# DR55_soundgen.net
KiCad netlist of a schematic drawn in EAGLE
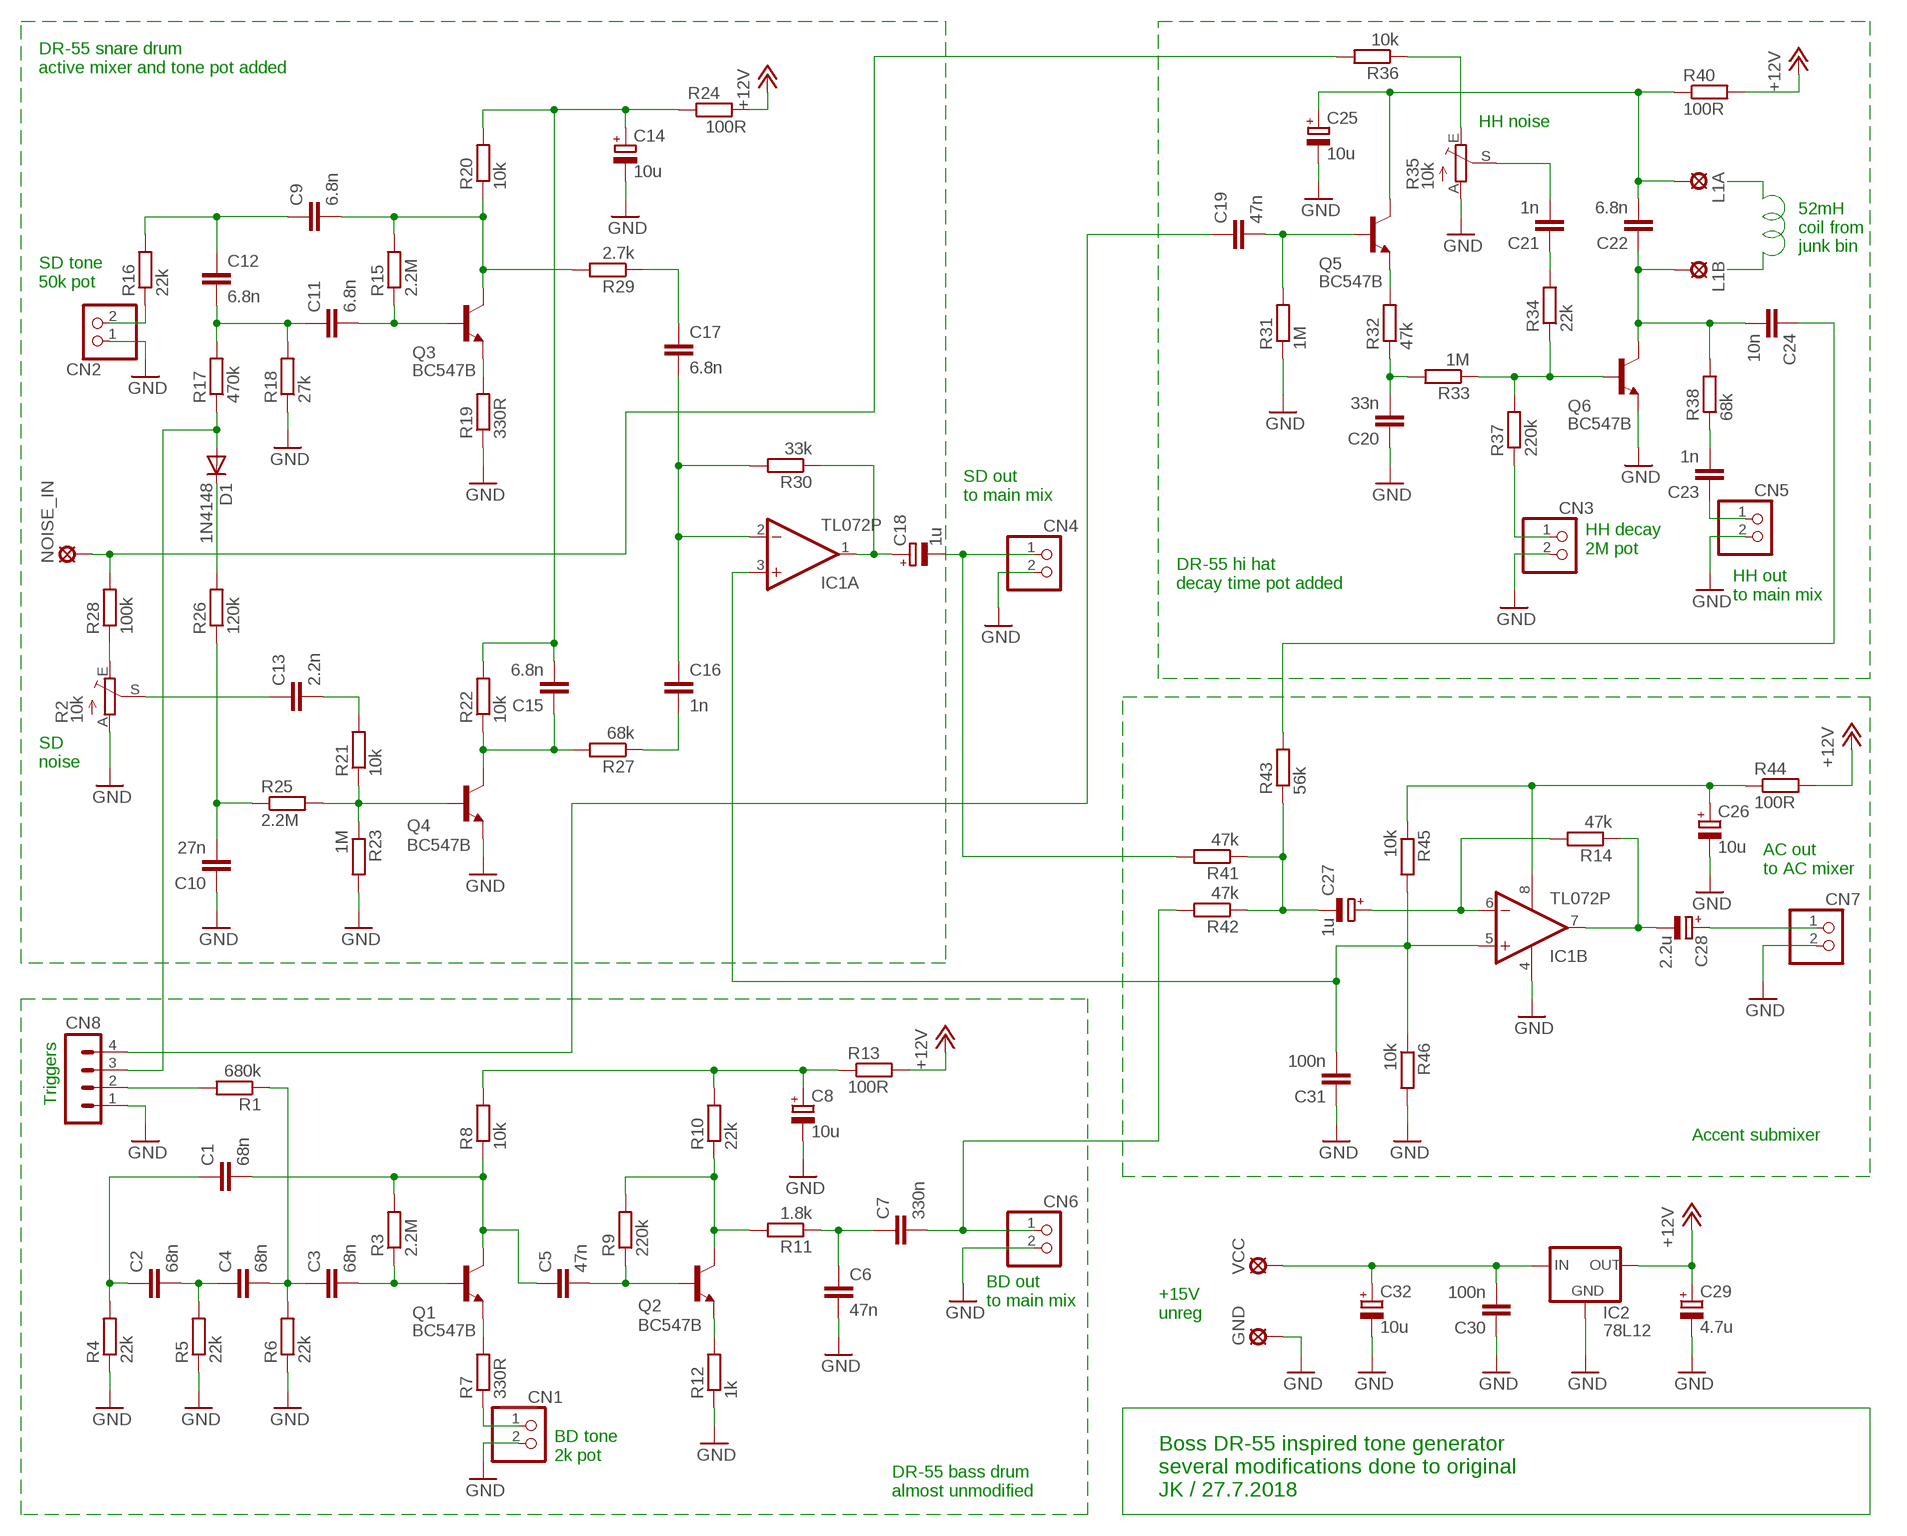
[diagram p0: schematic, sheet 1]

(export (version "E")
  (design (tool "Eeschema 10.0.6"))
  (components
    (comp (ref "C1")
      (value "68n")
      (footprint "eagle-import:C0805")
      (libsource (lib "eagle-import") (part "C-EUC0805"))
    )
    (comp (ref "C2")
      (value "68n")
      (footprint "eagle-import:C0805")
      (libsource (lib "eagle-import") (part "C-EUC0805"))
    )
    (comp (ref "C3")
      (value "68n")
      (footprint "eagle-import:C0805")
      (libsource (lib "eagle-import") (part "C-EUC0805"))
    )
    (comp (ref "C4")
      (value "68n")
      (footprint "eagle-import:C0805")
      (libsource (lib "eagle-import") (part "C-EUC0805"))
    )
    (comp (ref "C5")
      (value "47n")
      (footprint "eagle-import:C0805")
      (libsource (lib "eagle-import") (part "C-EUC0805"))
    )
    (comp (ref "C6")
      (value "47n")
      (footprint "eagle-import:C0805")
      (libsource (lib "eagle-import") (part "C-EUC0805"))
    )
    (comp (ref "C7")
      (value "330n")
      (footprint "eagle-import:C0805")
      (libsource (lib "eagle-import") (part "C-EUC0805"))
    )
    (comp (ref "C8")
      (value "10u")
      (footprint "eagle-import:E5-5")
      (libsource (lib "eagle-import") (part "CPOL-EUE5-5"))
    )
    (comp (ref "C9")
      (value "6.8n")
      (footprint "eagle-import:C0805")
      (libsource (lib "eagle-import") (part "C-EUC0805"))
    )
    (comp (ref "C10")
      (value "27n")
      (footprint "eagle-import:C0805")
      (libsource (lib "eagle-import") (part "C-EUC0805"))
    )
    (comp (ref "C11")
      (value "6.8n")
      (footprint "eagle-import:C0805")
      (libsource (lib "eagle-import") (part "C-EUC0805"))
    )
    (comp (ref "C12")
      (value "6.8n")
      (footprint "eagle-import:C0805")
      (libsource (lib "eagle-import") (part "C-EUC0805"))
    )
    (comp (ref "C13")
      (value "2.2n")
      (footprint "eagle-import:C0805")
      (libsource (lib "eagle-import") (part "C-EUC0805"))
    )
    (comp (ref "C14")
      (value "10u")
      (footprint "eagle-import:E5-5")
      (libsource (lib "eagle-import") (part "CPOL-EUE5-5"))
    )
    (comp (ref "C15")
      (value "6.8n")
      (footprint "eagle-import:C025-024X044")
      (libsource (lib "eagle-import") (part "C-EU025-024X044"))
    )
    (comp (ref "C16")
      (value "1n")
      (footprint "eagle-import:C0805")
      (libsource (lib "eagle-import") (part "C-EUC0805"))
    )
    (comp (ref "C17")
      (value "6.8n")
      (footprint "eagle-import:C0805")
      (libsource (lib "eagle-import") (part "C-EUC0805"))
    )
    (comp (ref "C18")
      (value "1u")
      (footprint "eagle-import:SMC_A")
      (libsource (lib "eagle-import") (part "CPOL-EUSMCA"))
    )
    (comp (ref "C19")
      (value "47n")
      (footprint "eagle-import:C0805")
      (libsource (lib "eagle-import") (part "C-EUC0805"))
    )
    (comp (ref "C20")
      (value "33n")
      (footprint "eagle-import:C0805")
      (libsource (lib "eagle-import") (part "C-EUC0805"))
    )
    (comp (ref "C21")
      (value "1n")
      (footprint "eagle-import:C0805")
      (libsource (lib "eagle-import") (part "C-EUC0805"))
    )
    (comp (ref "C22")
      (value "6.8n")
      (footprint "eagle-import:C0805")
      (libsource (lib "eagle-import") (part "C-EUC0805"))
    )
    (comp (ref "C23")
      (value "1n")
      (footprint "eagle-import:C0805")
      (libsource (lib "eagle-import") (part "C-EUC0805"))
    )
    (comp (ref "C24")
      (value "10n")
      (footprint "eagle-import:C0805")
      (libsource (lib "eagle-import") (part "C-EUC0805"))
    )
    (comp (ref "C25")
      (value "10u")
      (footprint "eagle-import:E5-5")
      (libsource (lib "eagle-import") (part "CPOL-EUE5-5"))
    )
    (comp (ref "C26")
      (value "10u")
      (footprint "eagle-import:E5-5")
      (libsource (lib "eagle-import") (part "CPOL-EUE5-5"))
    )
    (comp (ref "C27")
      (value "1u")
      (footprint "eagle-import:SMC_A")
      (libsource (lib "eagle-import") (part "CPOL-EUSMCA"))
    )
    (comp (ref "C28")
      (value "2.2u")
      (footprint "eagle-import:E5-5")
      (libsource (lib "eagle-import") (part "CPOL-EUE5-5"))
    )
    (comp (ref "C29")
      (value "4.7u")
      (footprint "eagle-import:SMC_A")
      (libsource (lib "eagle-import") (part "CPOL-EUSMCA"))
    )
    (comp (ref "C30")
      (value "100n")
      (footprint "eagle-import:C0805")
      (libsource (lib "eagle-import") (part "C-EUC0805"))
    )
    (comp (ref "C31")
      (value "100n")
      (footprint "eagle-import:C0805")
      (libsource (lib "eagle-import") (part "C-EUC0805"))
    )
    (comp (ref "C32")
      (value "10u")
      (footprint "eagle-import:E5-5")
      (libsource (lib "eagle-import") (part "CPOL-EUE5-5"))
    )
    (comp (ref "CN1")
      (value "PINHD-1X2")
      (footprint "eagle-import:1X02")
      (libsource (lib "eagle-import") (part "PINHD-1X2"))
    )
    (comp (ref "CN2")
      (value "PINHD-1X2")
      (footprint "eagle-import:1X02")
      (libsource (lib "eagle-import") (part "PINHD-1X2"))
    )
    (comp (ref "CN3")
      (value "PINHD-1X2")
      (footprint "eagle-import:1X02")
      (libsource (lib "eagle-import") (part "PINHD-1X2"))
    )
    (comp (ref "CN4")
      (value "PINHD-1X2")
      (footprint "eagle-import:1X02")
      (libsource (lib "eagle-import") (part "PINHD-1X2"))
    )
    (comp (ref "CN5")
      (value "PINHD-1X2")
      (footprint "eagle-import:1X02")
      (libsource (lib "eagle-import") (part "PINHD-1X2"))
    )
    (comp (ref "CN6")
      (value "PINHD-1X2")
      (footprint "eagle-import:1X02")
      (libsource (lib "eagle-import") (part "PINHD-1X2"))
    )
    (comp (ref "CN7")
      (value "PINHD-1X2")
      (footprint "eagle-import:1X02")
      (libsource (lib "eagle-import") (part "PINHD-1X2"))
    )
    (comp (ref "CN8")
      (value "MA04-1")
      (footprint "eagle-import:MA04-1")
      (libsource (lib "eagle-import") (part "MA04-1"))
    )
    (comp (ref "D1")
      (value "1N4148")
      (footprint "eagle-import:SOD80C")
      (libsource (lib "eagle-import") (part "DIODE-SOD80C"))
    )
    (comp (ref "GND")
      (value "LSP10")
      (footprint "eagle-import:LSP10")
      (libsource (lib "eagle-import") (part "LSP10"))
    )
    (comp (ref "IC1")
      (value "TL072P")
      (footprint "eagle-import:DIL08")
      (libsource (lib "eagle-import") (part "TL072P"))
    )
    (comp (ref "IC2")
      (value "78L12")
      (footprint "eagle-import:78LXX")
      (libsource (lib "eagle-import") (part "78LXX"))
    )
    (comp (ref "L1A")
      (value "MCS10B")
      (footprint "eagle-import:MCS10B")
      (libsource (lib "eagle-import") (part "MCS10B"))
    )
    (comp (ref "L1B")
      (value "MCS10B")
      (footprint "eagle-import:MCS10B")
      (libsource (lib "eagle-import") (part "MCS10B"))
    )
    (comp (ref "NOISE_IN")
      (value "LSP10")
      (footprint "eagle-import:LSP10")
      (libsource (lib "eagle-import") (part "LSP10"))
    )
    (comp (ref "Q1")
      (value "BC547B")
      (footprint "eagle-import:TO92")
      (libsource (lib "eagle-import") (part "BC547B"))
    )
    (comp (ref "Q2")
      (value "BC547B")
      (footprint "eagle-import:TO92")
      (libsource (lib "eagle-import") (part "BC547B"))
    )
    (comp (ref "Q3")
      (value "BC547B")
      (footprint "eagle-import:TO92")
      (libsource (lib "eagle-import") (part "BC547B"))
    )
    (comp (ref "Q4")
      (value "BC547B")
      (footprint "eagle-import:TO92")
      (libsource (lib "eagle-import") (part "BC547B"))
    )
    (comp (ref "Q5")
      (value "BC547B")
      (footprint "eagle-import:TO92")
      (libsource (lib "eagle-import") (part "BC547B"))
    )
    (comp (ref "Q6")
      (value "BC547B")
      (footprint "eagle-import:TO92")
      (libsource (lib "eagle-import") (part "BC547B"))
    )
    (comp (ref "R1")
      (value "680k")
      (footprint "eagle-import:R0805")
      (libsource (lib "eagle-import") (part "R-EU_R0805"))
    )
    (comp (ref "R2")
      (value "10k")
      (footprint "eagle-import:S63X")
      (libsource (lib "eagle-import") (part "TRIM_EU-S63X"))
    )
    (comp (ref "R3")
      (value "2.2M")
      (footprint "eagle-import:R0805")
      (libsource (lib "eagle-import") (part "R-EU_R0805"))
    )
    (comp (ref "R4")
      (value "22k")
      (footprint "eagle-import:R0805")
      (libsource (lib "eagle-import") (part "R-EU_R0805"))
    )
    (comp (ref "R5")
      (value "22k")
      (footprint "eagle-import:R0805")
      (libsource (lib "eagle-import") (part "R-EU_R0805"))
    )
    (comp (ref "R6")
      (value "22k")
      (footprint "eagle-import:R0805")
      (libsource (lib "eagle-import") (part "R-EU_R0805"))
    )
    (comp (ref "R7")
      (value "330R")
      (footprint "eagle-import:R0805")
      (libsource (lib "eagle-import") (part "R-EU_R0805"))
    )
    (comp (ref "R8")
      (value "10k")
      (footprint "eagle-import:R0805")
      (libsource (lib "eagle-import") (part "R-EU_R0805"))
    )
    (comp (ref "R9")
      (value "220k")
      (footprint "eagle-import:R0805")
      (libsource (lib "eagle-import") (part "R-EU_R0805"))
    )
    (comp (ref "R10")
      (value "22k")
      (footprint "eagle-import:R0805")
      (libsource (lib "eagle-import") (part "R-EU_R0805"))
    )
    (comp (ref "R11")
      (value "1.8k")
      (footprint "eagle-import:R0805")
      (libsource (lib "eagle-import") (part "R-EU_R0805"))
    )
    (comp (ref "R12")
      (value "1k")
      (footprint "eagle-import:R0805")
      (libsource (lib "eagle-import") (part "R-EU_R0805"))
    )
    (comp (ref "R13")
      (value "100R")
      (footprint "eagle-import:R0805")
      (libsource (lib "eagle-import") (part "R-EU_R0805"))
    )
    (comp (ref "R14")
      (value "47k")
      (footprint "eagle-import:R0805")
      (libsource (lib "eagle-import") (part "R-EU_R0805"))
    )
    (comp (ref "R15")
      (value "2.2M")
      (footprint "eagle-import:R0805")
      (libsource (lib "eagle-import") (part "R-EU_R0805"))
    )
    (comp (ref "R16")
      (value "22k")
      (footprint "eagle-import:R0805")
      (libsource (lib "eagle-import") (part "R-EU_R0805"))
    )
    (comp (ref "R17")
      (value "470k")
      (footprint "eagle-import:R0805")
      (libsource (lib "eagle-import") (part "R-EU_R0805"))
    )
    (comp (ref "R18")
      (value "27k")
      (footprint "eagle-import:R0805")
      (libsource (lib "eagle-import") (part "R-EU_R0805"))
    )
    (comp (ref "R19")
      (value "330R")
      (footprint "eagle-import:R0805")
      (libsource (lib "eagle-import") (part "R-EU_R0805"))
    )
    (comp (ref "R20")
      (value "10k")
      (footprint "eagle-import:R0805")
      (libsource (lib "eagle-import") (part "R-EU_R0805"))
    )
    (comp (ref "R21")
      (value "10k")
      (footprint "eagle-import:R0805")
      (libsource (lib "eagle-import") (part "R-EU_R0805"))
    )
    (comp (ref "R22")
      (value "10k")
      (footprint "eagle-import:R0805")
      (libsource (lib "eagle-import") (part "R-EU_R0805"))
    )
    (comp (ref "R23")
      (value "1M")
      (footprint "eagle-import:R0805")
      (libsource (lib "eagle-import") (part "R-EU_R0805"))
    )
    (comp (ref "R24")
      (value "100R")
      (footprint "eagle-import:R0805")
      (libsource (lib "eagle-import") (part "R-EU_R0805"))
    )
    (comp (ref "R25")
      (value "2.2M")
      (footprint "eagle-import:R0805")
      (libsource (lib "eagle-import") (part "R-EU_R0805"))
    )
    (comp (ref "R26")
      (value "120k")
      (footprint "eagle-import:R0805")
      (libsource (lib "eagle-import") (part "R-EU_R0805"))
    )
    (comp (ref "R27")
      (value "68k")
      (footprint "eagle-import:R0805")
      (libsource (lib "eagle-import") (part "R-EU_R0805"))
    )
    (comp (ref "R28")
      (value "100k")
      (footprint "eagle-import:R0805")
      (libsource (lib "eagle-import") (part "R-EU_R0805"))
    )
    (comp (ref "R29")
      (value "2.7k")
      (footprint "eagle-import:R0805")
      (libsource (lib "eagle-import") (part "R-EU_R0805"))
    )
    (comp (ref "R30")
      (value "33k")
      (footprint "eagle-import:R0805")
      (libsource (lib "eagle-import") (part "R-EU_R0805"))
    )
    (comp (ref "R31")
      (value "1M")
      (footprint "eagle-import:R0805")
      (libsource (lib "eagle-import") (part "R-EU_R0805"))
    )
    (comp (ref "R32")
      (value "47k")
      (footprint "eagle-import:0207_10")
      (libsource (lib "eagle-import") (part "R-EU_0207/10"))
    )
    (comp (ref "R33")
      (value "1M")
      (footprint "eagle-import:R0805")
      (libsource (lib "eagle-import") (part "R-EU_R0805"))
    )
    (comp (ref "R34")
      (value "22k")
      (footprint "eagle-import:R0805")
      (libsource (lib "eagle-import") (part "R-EU_R0805"))
    )
    (comp (ref "R35")
      (value "10k")
      (footprint "eagle-import:S63X")
      (libsource (lib "eagle-import") (part "TRIM_EU-S63X"))
    )
    (comp (ref "R36")
      (value "10k")
      (footprint "eagle-import:R0805")
      (libsource (lib "eagle-import") (part "R-EU_R0805"))
    )
    (comp (ref "R37")
      (value "220k")
      (footprint "eagle-import:R0805")
      (libsource (lib "eagle-import") (part "R-EU_R0805"))
    )
    (comp (ref "R38")
      (value "68k")
      (footprint "eagle-import:R0805")
      (libsource (lib "eagle-import") (part "R-EU_R0805"))
    )
    (comp (ref "R40")
      (value "100R")
      (footprint "eagle-import:R0805")
      (libsource (lib "eagle-import") (part "R-EU_R0805"))
    )
    (comp (ref "R41")
      (value "47k")
      (footprint "eagle-import:R0805")
      (libsource (lib "eagle-import") (part "R-EU_R0805"))
    )
    (comp (ref "R42")
      (value "47k")
      (footprint "eagle-import:R0805")
      (libsource (lib "eagle-import") (part "R-EU_R0805"))
    )
    (comp (ref "R43")
      (value "56k")
      (footprint "eagle-import:R0805")
      (libsource (lib "eagle-import") (part "R-EU_R0805"))
    )
    (comp (ref "R44")
      (value "100R")
      (footprint "eagle-import:R0805")
      (libsource (lib "eagle-import") (part "R-EU_R0805"))
    )
    (comp (ref "R45")
      (value "10k")
      (footprint "eagle-import:R0805")
      (libsource (lib "eagle-import") (part "R-EU_R0805"))
    )
    (comp (ref "R46")
      (value "10k")
      (footprint "eagle-import:R0805")
      (libsource (lib "eagle-import") (part "R-EU_R0805"))
    )
    (comp (ref "VCC")
      (value "LSP10")
      (footprint "eagle-import:LSP10")
      (libsource (lib "eagle-import") (part "LSP10"))
    )
  )
  (nets
    (net (code "1") (name "+12V") (class "Default")
      (node (ref "C29") (pin "+") (pinfunction "+_+") (pintype "passive"))
      (node (ref "IC2") (pin "OUT") (pinfunction "OUT_OUT") (pintype "passive"))
      (node (ref "R13") (pin "2") (pinfunction "2_2") (pintype "passive"))
      (node (ref "R24") (pin "2") (pinfunction "2_2") (pintype "passive"))
      (node (ref "R40") (pin "2") (pinfunction "2_2") (pintype "passive"))
      (node (ref "R44") (pin "2") (pinfunction "2_2") (pintype "passive"))
    )
    (net (code "2") (name "GND") (class "Default")
      (node (ref "C10") (pin "1") (pinfunction "1_1") (pintype "passive"))
      (node (ref "C14") (pin "-") (pinfunction "-_-") (pintype "passive"))
      (node (ref "C20") (pin "1") (pinfunction "1_1") (pintype "passive"))
      (node (ref "C25") (pin "-") (pinfunction "-_-") (pintype "passive"))
      (node (ref "C26") (pin "-") (pinfunction "-_-") (pintype "passive"))
      (node (ref "C29") (pin "-") (pinfunction "-_-") (pintype "passive"))
      (node (ref "C30") (pin "1") (pinfunction "1_1") (pintype "passive"))
      (node (ref "C31") (pin "1") (pinfunction "1_1") (pintype "passive"))
      (node (ref "C32") (pin "-") (pinfunction "-_-") (pintype "passive"))
      (node (ref "C6") (pin "2") (pinfunction "2_2") (pintype "passive"))
      (node (ref "C8") (pin "-") (pinfunction "-_-") (pintype "passive"))
      (node (ref "CN1") (pin "2") (pinfunction "2_2") (pintype "passive"))
      (node (ref "CN2") (pin "1") (pinfunction "1_1") (pintype "passive"))
      (node (ref "CN3") (pin "2") (pinfunction "2_2") (pintype "passive"))
      (node (ref "CN4") (pin "2") (pinfunction "2_2") (pintype "passive"))
      (node (ref "CN5") (pin "2") (pinfunction "2_2") (pintype "passive"))
      (node (ref "CN6") (pin "2") (pinfunction "2_2") (pintype "passive"))
      (node (ref "CN7") (pin "2") (pinfunction "2_2") (pintype "passive"))
      (node (ref "CN8") (pin "1") (pinfunction "1_1") (pintype "passive"))
      (node (ref "GND") (pin "MP") (pinfunction "MP_MP") (pintype "passive"))
      (node (ref "IC1") (pin "4") (pinfunction "V-_4") (pintype "power_in"))
      (node (ref "IC2") (pin "GND") (pinfunction "GND_GND") (pintype "input"))
      (node (ref "Q4") (pin "1") (pinfunction "E_1") (pintype "passive"))
      (node (ref "Q6") (pin "1") (pinfunction "E_1") (pintype "passive"))
      (node (ref "R12") (pin "1") (pinfunction "1_1") (pintype "passive"))
      (node (ref "R18") (pin "1") (pinfunction "1_1") (pintype "passive"))
      (node (ref "R19") (pin "1") (pinfunction "1_1") (pintype "passive"))
      (node (ref "R2") (pin "A") (pinfunction "A_A") (pintype "passive"))
      (node (ref "R23") (pin "2") (pinfunction "2_2") (pintype "passive"))
      (node (ref "R31") (pin "1") (pinfunction "1_1") (pintype "passive"))
      (node (ref "R35") (pin "A") (pinfunction "A_A") (pintype "passive"))
      (node (ref "R4") (pin "1") (pinfunction "1_1") (pintype "passive"))
      (node (ref "R46") (pin "2") (pinfunction "2_2") (pintype "passive"))
      (node (ref "R5") (pin "1") (pinfunction "1_1") (pintype "passive"))
      (node (ref "R6") (pin "1") (pinfunction "1_1") (pintype "passive"))
    )
    (net (code "3") (name "Net-(C1-Pad1)") (class "Default")
      (node (ref "C1") (pin "1") (pinfunction "1_1") (pintype "passive"))
      (node (ref "C2") (pin "1") (pinfunction "1_1") (pintype "passive"))
      (node (ref "R4") (pin "2") (pinfunction "2_2") (pintype "passive"))
    )
    (net (code "4") (name "Net-(C2-Pad2)") (class "Default")
      (node (ref "C2") (pin "2") (pinfunction "2_2") (pintype "passive"))
      (node (ref "C4") (pin "1") (pinfunction "1_1") (pintype "passive"))
      (node (ref "R5") (pin "2") (pinfunction "2_2") (pintype "passive"))
    )
    (net (code "5") (name "Net-(C3-Pad1)") (class "Default")
      (node (ref "C3") (pin "1") (pinfunction "1_1") (pintype "passive"))
      (node (ref "C4") (pin "2") (pinfunction "2_2") (pintype "passive"))
      (node (ref "R1") (pin "1") (pinfunction "1_1") (pintype "passive"))
      (node (ref "R6") (pin "2") (pinfunction "2_2") (pintype "passive"))
    )
    (net (code "6") (name "Net-(C6-Pad1)") (class "Default")
      (node (ref "C6") (pin "1") (pinfunction "1_1") (pintype "passive"))
      (node (ref "C7") (pin "1") (pinfunction "1_1") (pintype "passive"))
      (node (ref "R11") (pin "1") (pinfunction "1_1") (pintype "passive"))
    )
    (net (code "7") (name "Net-(C7-Pad2)") (class "Default")
      (node (ref "C7") (pin "2") (pinfunction "2_2") (pintype "passive"))
      (node (ref "CN6") (pin "1") (pinfunction "1_1") (pintype "passive"))
      (node (ref "R42") (pin "2") (pinfunction "2_2") (pintype "passive"))
    )
    (net (code "8") (name "Net-(C8-Pad+)") (class "Default")
      (node (ref "C8") (pin "+") (pinfunction "+_+") (pintype "passive"))
      (node (ref "R10") (pin "2") (pinfunction "2_2") (pintype "passive"))
      (node (ref "R13") (pin "1") (pinfunction "1_1") (pintype "passive"))
      (node (ref "R8") (pin "2") (pinfunction "2_2") (pintype "passive"))
    )
    (net (code "9") (name "Net-(C10-Pad2)") (class "Default")
      (node (ref "C10") (pin "2") (pinfunction "2_2") (pintype "passive"))
      (node (ref "R25") (pin "1") (pinfunction "1_1") (pintype "passive"))
      (node (ref "R26") (pin "1") (pinfunction "1_1") (pintype "passive"))
    )
    (net (code "10") (name "Net-(C11-Pad1)") (class "Default")
      (node (ref "C11") (pin "1") (pinfunction "1_1") (pintype "passive"))
      (node (ref "C12") (pin "2") (pinfunction "2_2") (pintype "passive"))
      (node (ref "R17") (pin "2") (pinfunction "2_2") (pintype "passive"))
      (node (ref "R18") (pin "2") (pinfunction "2_2") (pintype "passive"))
    )
    (net (code "11") (name "Net-(C12-Pad1)") (class "Default")
      (node (ref "C12") (pin "1") (pinfunction "1_1") (pintype "passive"))
      (node (ref "C9") (pin "1") (pinfunction "1_1") (pintype "passive"))
      (node (ref "R16") (pin "2") (pinfunction "2_2") (pintype "passive"))
    )
    (net (code "12") (name "Net-(C13-Pad1)") (class "Default")
      (node (ref "C13") (pin "1") (pinfunction "1_1") (pintype "passive"))
      (node (ref "R2") (pin "S") (pinfunction "S_S") (pintype "passive"))
    )
    (net (code "13") (name "Net-(C13-Pad2)") (class "Default")
      (node (ref "C13") (pin "2") (pinfunction "2_2") (pintype "passive"))
      (node (ref "R21") (pin "2") (pinfunction "2_2") (pintype "passive"))
    )
    (net (code "14") (name "Net-(C14-Pad+)") (class "Default")
      (node (ref "C14") (pin "+") (pinfunction "+_+") (pintype "passive"))
      (node (ref "C15") (pin "2") (pinfunction "2_2") (pintype "passive"))
      (node (ref "R20") (pin "2") (pinfunction "2_2") (pintype "passive"))
      (node (ref "R22") (pin "2") (pinfunction "2_2") (pintype "passive"))
      (node (ref "R24") (pin "1") (pinfunction "1_1") (pintype "passive"))
    )
    (net (code "15") (name "Net-(C16-Pad2)") (class "Default")
      (node (ref "C16") (pin "2") (pinfunction "2_2") (pintype "passive"))
      (node (ref "R27") (pin "1") (pinfunction "1_1") (pintype "passive"))
    )
    (net (code "16") (name "Net-(C17-Pad1)") (class "Default")
      (node (ref "C17") (pin "1") (pinfunction "1_1") (pintype "passive"))
      (node (ref "R29") (pin "1") (pinfunction "1_1") (pintype "passive"))
    )
    (net (code "17") (name "Net-(C18-Pad-)") (class "Default")
      (node (ref "C18") (pin "-") (pinfunction "-_-") (pintype "passive"))
      (node (ref "CN4") (pin "1") (pinfunction "1_1") (pintype "passive"))
      (node (ref "R41") (pin "2") (pinfunction "2_2") (pintype "passive"))
    )
    (net (code "18") (name "Net-(C19-Pad1)") (class "Default")
      (node (ref "C19") (pin "1") (pinfunction "1_1") (pintype "passive"))
      (node (ref "CN8") (pin "4") (pinfunction "4_4") (pintype "passive"))
    )
    (net (code "19") (name "Net-(C20-Pad2)") (class "Default")
      (node (ref "C20") (pin "2") (pinfunction "2_2") (pintype "passive"))
      (node (ref "R32") (pin "1") (pinfunction "1_1") (pintype "passive"))
      (node (ref "R33") (pin "2") (pinfunction "2_2") (pintype "passive"))
    )
    (net (code "20") (name "Net-(C21-Pad1)") (class "Default")
      (node (ref "C21") (pin "1") (pinfunction "1_1") (pintype "passive"))
      (node (ref "R34") (pin "2") (pinfunction "2_2") (pintype "passive"))
    )
    (net (code "21") (name "Net-(C21-Pad2)") (class "Default")
      (node (ref "C21") (pin "2") (pinfunction "2_2") (pintype "passive"))
      (node (ref "R35") (pin "S") (pinfunction "S_S") (pintype "passive"))
    )
    (net (code "22") (name "Net-(C23-Pad1)") (class "Default")
      (node (ref "C23") (pin "1") (pinfunction "1_1") (pintype "passive"))
      (node (ref "CN5") (pin "1") (pinfunction "1_1") (pintype "passive"))
    )
    (net (code "23") (name "Net-(C23-Pad2)") (class "Default")
      (node (ref "C23") (pin "2") (pinfunction "2_2") (pintype "passive"))
      (node (ref "R38") (pin "1") (pinfunction "1_1") (pintype "passive"))
    )
    (net (code "24") (name "Net-(C24-Pad1)") (class "Default")
      (node (ref "C24") (pin "1") (pinfunction "1_1") (pintype "passive"))
      (node (ref "R43") (pin "2") (pinfunction "2_2") (pintype "passive"))
    )
    (net (code "25") (name "Net-(C27-Pad-)") (class "Default")
      (node (ref "C27") (pin "-") (pinfunction "-_-") (pintype "passive"))
      (node (ref "R41") (pin "1") (pinfunction "1_1") (pintype "passive"))
      (node (ref "R42") (pin "1") (pinfunction "1_1") (pintype "passive"))
      (node (ref "R43") (pin "1") (pinfunction "1_1") (pintype "passive"))
    )
    (net (code "26") (name "Net-(C28-Pad+)") (class "Default")
      (node (ref "C28") (pin "+") (pinfunction "+_+") (pintype "passive"))
      (node (ref "CN7") (pin "1") (pinfunction "1_1") (pintype "passive"))
    )
    (net (code "27") (name "Net-(C30-Pad2)") (class "Default")
      (node (ref "C30") (pin "2") (pinfunction "2_2") (pintype "passive"))
      (node (ref "C32") (pin "+") (pinfunction "+_+") (pintype "passive"))
      (node (ref "IC2") (pin "IN") (pinfunction "IN_IN") (pintype "input"))
      (node (ref "VCC") (pin "MP") (pinfunction "MP_MP") (pintype "passive"))
    )
    (net (code "28") (name "Net-(CN1-Pad1)") (class "Default")
      (node (ref "CN1") (pin "1") (pinfunction "1_1") (pintype "passive"))
      (node (ref "R7") (pin "1") (pinfunction "1_1") (pintype "passive"))
    )
    (net (code "29") (name "Net-(CN2-Pad2)") (class "Default")
      (node (ref "CN2") (pin "2") (pinfunction "2_2") (pintype "passive"))
      (node (ref "R16") (pin "1") (pinfunction "1_1") (pintype "passive"))
    )
    (net (code "30") (name "Net-(CN3-Pad1)") (class "Default")
      (node (ref "CN3") (pin "1") (pinfunction "1_1") (pintype "passive"))
      (node (ref "R37") (pin "1") (pinfunction "1_1") (pintype "passive"))
    )
    (net (code "31") (name "Net-(CN8-Pad2)") (class "Default")
      (node (ref "CN8") (pin "2") (pinfunction "2_2") (pintype "passive"))
      (node (ref "R1") (pin "2") (pinfunction "2_2") (pintype "passive"))
    )
    (net (code "32") (name "Net-(CN8-Pad3)") (class "Default")
      (node (ref "CN8") (pin "3") (pinfunction "3_3") (pintype "passive"))
      (node (ref "D1") (pin "A") (pinfunction "A_A") (pintype "passive"))
      (node (ref "R17") (pin "1") (pinfunction "1_1") (pintype "passive"))
    )
    (net (code "33") (name "Net-(D1-PadC)") (class "Default")
      (node (ref "D1") (pin "C") (pinfunction "C_C") (pintype "passive"))
      (node (ref "R26") (pin "2") (pinfunction "2_2") (pintype "passive"))
    )
    (net (code "34") (name "Net-(IC1A-+IN)") (class "Default")
      (node (ref "C31") (pin "2") (pinfunction "2_2") (pintype "passive"))
      (node (ref "IC1") (pin "3") (pinfunction "+IN_3") (pintype "input"))
      (node (ref "IC1") (pin "5") (pinfunction "+IN_5") (pintype "input"))
      (node (ref "R45") (pin "2") (pinfunction "2_2") (pintype "passive"))
      (node (ref "R46") (pin "1") (pinfunction "1_1") (pintype "passive"))
    )
    (net (code "35") (name "Net-(IC1A--IN)") (class "Default")
      (node (ref "C16") (pin "1") (pinfunction "1_1") (pintype "passive"))
      (node (ref "C17") (pin "2") (pinfunction "2_2") (pintype "passive"))
      (node (ref "IC1") (pin "2") (pinfunction "-IN_2") (pintype "input"))
      (node (ref "R30") (pin "2") (pinfunction "2_2") (pintype "passive"))
    )
    (net (code "36") (name "Net-(IC1A-OUT)") (class "Default")
      (node (ref "C18") (pin "+") (pinfunction "+_+") (pintype "passive"))
      (node (ref "IC1") (pin "1") (pinfunction "OUT_1") (pintype "output"))
      (node (ref "R30") (pin "1") (pinfunction "1_1") (pintype "passive"))
    )
    (net (code "37") (name "Net-(IC1B--IN)") (class "Default")
      (node (ref "C27") (pin "+") (pinfunction "+_+") (pintype "passive"))
      (node (ref "IC1") (pin "6") (pinfunction "-IN_6") (pintype "input"))
      (node (ref "R14") (pin "2") (pinfunction "2_2") (pintype "passive"))
    )
    (net (code "38") (name "Net-(IC1B-OUT)") (class "Default")
      (node (ref "C28") (pin "-") (pinfunction "-_-") (pintype "passive"))
      (node (ref "IC1") (pin "7") (pinfunction "OUT_7") (pintype "output"))
      (node (ref "R14") (pin "1") (pinfunction "1_1") (pintype "passive"))
    )
    (net (code "39") (name "Net-(IC1C-V+)") (class "Default")
      (node (ref "C26") (pin "+") (pinfunction "+_+") (pintype "passive"))
      (node (ref "IC1") (pin "8") (pinfunction "V+_8") (pintype "power_in"))
      (node (ref "R44") (pin "1") (pinfunction "1_1") (pintype "passive"))
      (node (ref "R45") (pin "1") (pinfunction "1_1") (pintype "passive"))
    )
    (net (code "40") (name "Net-(NOISE_IN-PadMP)") (class "Default")
      (node (ref "NOISE_IN") (pin "MP") (pinfunction "MP_MP") (pintype "passive"))
      (node (ref "R28") (pin "2") (pinfunction "2_2") (pintype "passive"))
      (node (ref "R36") (pin "2") (pinfunction "2_2") (pintype "passive"))
    )
    (net (code "41") (name "Net-(Q1-B)") (class "Default")
      (node (ref "C3") (pin "2") (pinfunction "2_2") (pintype "passive"))
      (node (ref "Q1") (pin "2") (pinfunction "B_2") (pintype "passive"))
      (node (ref "R3") (pin "1") (pinfunction "1_1") (pintype "passive"))
    )
    (net (code "42") (name "Net-(Q1-C)") (class "Default")
      (node (ref "C1") (pin "2") (pinfunction "2_2") (pintype "passive"))
      (node (ref "C5") (pin "1") (pinfunction "1_1") (pintype "passive"))
      (node (ref "Q1") (pin "3") (pinfunction "C_3") (pintype "passive"))
      (node (ref "R3") (pin "2") (pinfunction "2_2") (pintype "passive"))
      (node (ref "R8") (pin "1") (pinfunction "1_1") (pintype "passive"))
    )
    (net (code "43") (name "Net-(Q1-E)") (class "Default")
      (node (ref "Q1") (pin "1") (pinfunction "E_1") (pintype "passive"))
      (node (ref "R7") (pin "2") (pinfunction "2_2") (pintype "passive"))
    )
    (net (code "44") (name "Net-(Q2-B)") (class "Default")
      (node (ref "C5") (pin "2") (pinfunction "2_2") (pintype "passive"))
      (node (ref "Q2") (pin "2") (pinfunction "B_2") (pintype "passive"))
      (node (ref "R9") (pin "1") (pinfunction "1_1") (pintype "passive"))
    )
    (net (code "45") (name "Net-(Q2-C)") (class "Default")
      (node (ref "Q2") (pin "3") (pinfunction "C_3") (pintype "passive"))
      (node (ref "R10") (pin "1") (pinfunction "1_1") (pintype "passive"))
      (node (ref "R11") (pin "2") (pinfunction "2_2") (pintype "passive"))
      (node (ref "R9") (pin "2") (pinfunction "2_2") (pintype "passive"))
    )
    (net (code "46") (name "Net-(Q2-E)") (class "Default")
      (node (ref "Q2") (pin "1") (pinfunction "E_1") (pintype "passive"))
      (node (ref "R12") (pin "2") (pinfunction "2_2") (pintype "passive"))
    )
    (net (code "47") (name "Net-(Q3-B)") (class "Default")
      (node (ref "C11") (pin "2") (pinfunction "2_2") (pintype "passive"))
      (node (ref "Q3") (pin "2") (pinfunction "B_2") (pintype "passive"))
      (node (ref "R15") (pin "1") (pinfunction "1_1") (pintype "passive"))
    )
    (net (code "48") (name "Net-(Q3-C)") (class "Default")
      (node (ref "C9") (pin "2") (pinfunction "2_2") (pintype "passive"))
      (node (ref "Q3") (pin "3") (pinfunction "C_3") (pintype "passive"))
      (node (ref "R15") (pin "2") (pinfunction "2_2") (pintype "passive"))
      (node (ref "R20") (pin "1") (pinfunction "1_1") (pintype "passive"))
      (node (ref "R29") (pin "2") (pinfunction "2_2") (pintype "passive"))
    )
    (net (code "49") (name "Net-(Q3-E)") (class "Default")
      (node (ref "Q3") (pin "1") (pinfunction "E_1") (pintype "passive"))
      (node (ref "R19") (pin "2") (pinfunction "2_2") (pintype "passive"))
    )
    (net (code "50") (name "Net-(Q4-B)") (class "Default")
      (node (ref "Q4") (pin "2") (pinfunction "B_2") (pintype "passive"))
      (node (ref "R21") (pin "1") (pinfunction "1_1") (pintype "passive"))
      (node (ref "R23") (pin "1") (pinfunction "1_1") (pintype "passive"))
      (node (ref "R25") (pin "2") (pinfunction "2_2") (pintype "passive"))
    )
    (net (code "51") (name "Net-(Q4-C)") (class "Default")
      (node (ref "C15") (pin "1") (pinfunction "1_1") (pintype "passive"))
      (node (ref "Q4") (pin "3") (pinfunction "C_3") (pintype "passive"))
      (node (ref "R22") (pin "1") (pinfunction "1_1") (pintype "passive"))
      (node (ref "R27") (pin "2") (pinfunction "2_2") (pintype "passive"))
    )
    (net (code "52") (name "Net-(Q5-B)") (class "Default")
      (node (ref "C19") (pin "2") (pinfunction "2_2") (pintype "passive"))
      (node (ref "Q5") (pin "2") (pinfunction "B_2") (pintype "passive"))
      (node (ref "R31") (pin "2") (pinfunction "2_2") (pintype "passive"))
    )
    (net (code "53") (name "Net-(Q5-C)") (class "Default")
      (node (ref "C22") (pin "2") (pinfunction "2_2") (pintype "passive"))
      (node (ref "C25") (pin "+") (pinfunction "+_+") (pintype "passive"))
      (node (ref "L1A") (pin "MP") (pinfunction "MP_MP") (pintype "passive"))
      (node (ref "Q5") (pin "3") (pinfunction "C_3") (pintype "passive"))
      (node (ref "R40") (pin "1") (pinfunction "1_1") (pintype "passive"))
    )
    (net (code "54") (name "Net-(Q5-E)") (class "Default")
      (node (ref "Q5") (pin "1") (pinfunction "E_1") (pintype "passive"))
      (node (ref "R32") (pin "2") (pinfunction "2_2") (pintype "passive"))
    )
    (net (code "55") (name "Net-(Q6-B)") (class "Default")
      (node (ref "Q6") (pin "2") (pinfunction "B_2") (pintype "passive"))
      (node (ref "R33") (pin "1") (pinfunction "1_1") (pintype "passive"))
      (node (ref "R34") (pin "1") (pinfunction "1_1") (pintype "passive"))
      (node (ref "R37") (pin "2") (pinfunction "2_2") (pintype "passive"))
    )
    (net (code "56") (name "Net-(Q6-C)") (class "Default")
      (node (ref "C22") (pin "1") (pinfunction "1_1") (pintype "passive"))
      (node (ref "C24") (pin "2") (pinfunction "2_2") (pintype "passive"))
      (node (ref "L1B") (pin "MP") (pinfunction "MP_MP") (pintype "passive"))
      (node (ref "Q6") (pin "3") (pinfunction "C_3") (pintype "passive"))
      (node (ref "R38") (pin "2") (pinfunction "2_2") (pintype "passive"))
    )
    (net (code "57") (name "Net-(R2-PadE)") (class "Default")
      (node (ref "R2") (pin "E") (pinfunction "E_E") (pintype "passive"))
      (node (ref "R28") (pin "1") (pinfunction "1_1") (pintype "passive"))
    )
    (net (code "58") (name "Net-(R35-PadE)") (class "Default")
      (node (ref "R35") (pin "E") (pinfunction "E_E") (pintype "passive"))
      (node (ref "R36") (pin "1") (pinfunction "1_1") (pintype "passive"))
    )
  )
)
